# STM32WL_RF.net
KiCad netlist of a schematic drawn in Altium Designer
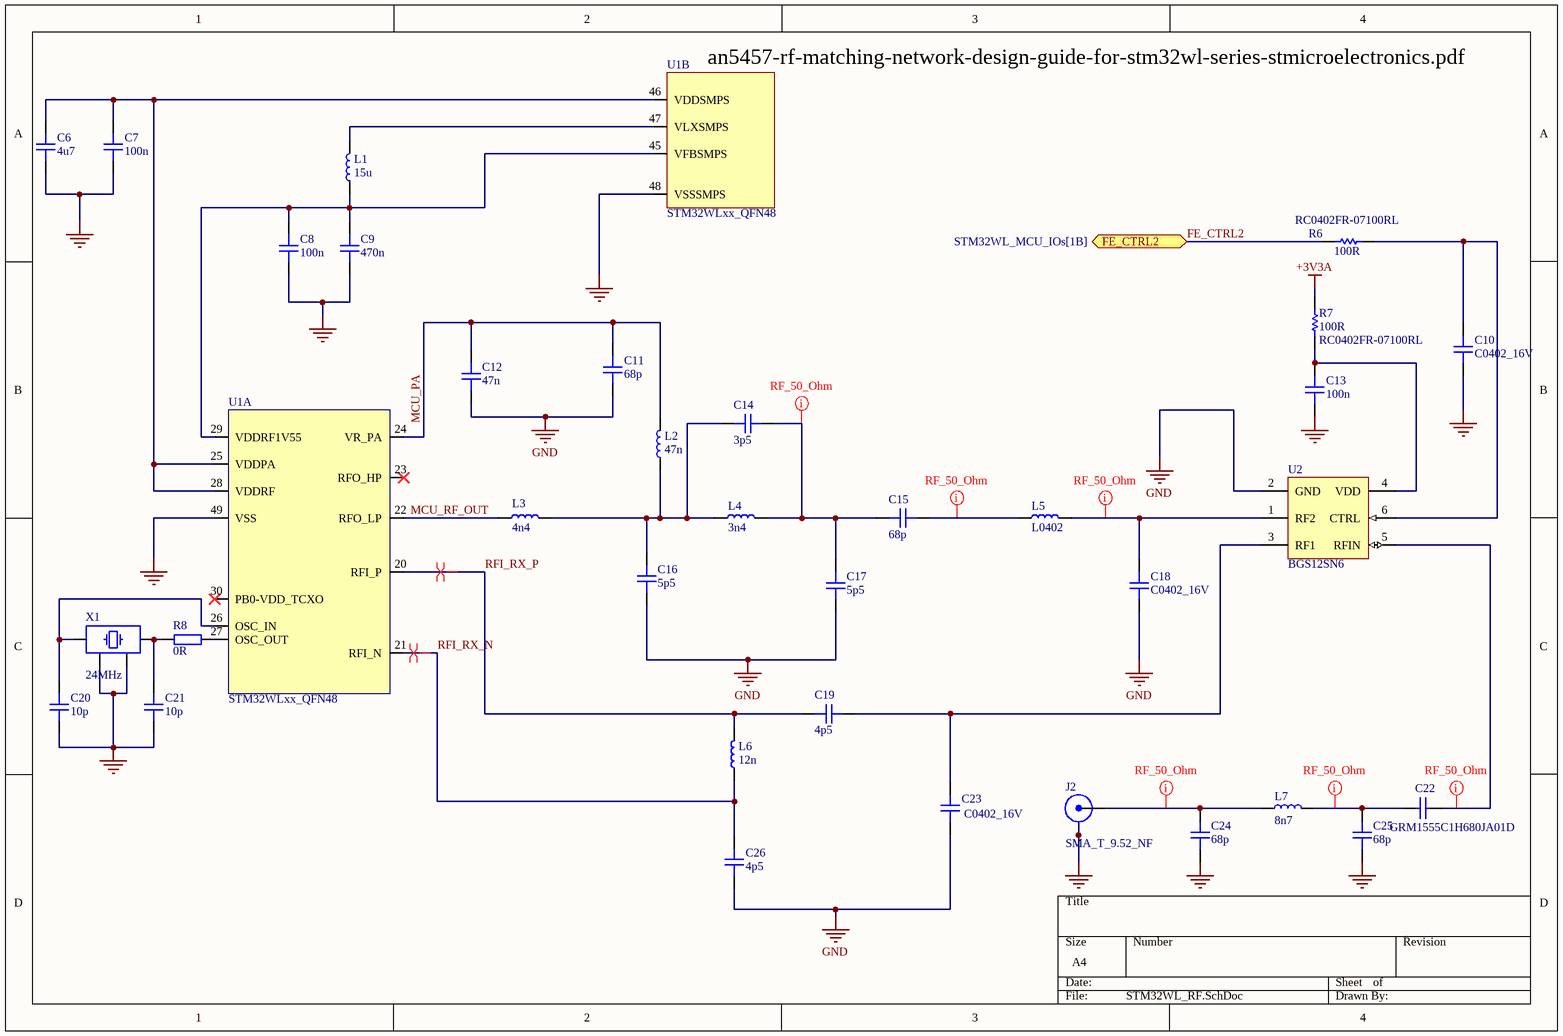
[diagram p0: STM32WL_RF.SchDoc]

(export (version "E")
  (design (tool "Eeschema 10.0.6"))
  (components
    (comp (ref "C6")
      (value "4u7")
      (footprint "CAP_0603")
      (description "Capacitor SMD 0201 16V")
      (libsource (lib "Schematic-Lib-PhilsLab") (part "CAP_0201_16V"))
    )
    (comp (ref "C7")
      (value "100n")
      (footprint "CAP_0603")
      (description "Capacitor SMD 0201 16V")
      (libsource (lib "Schematic-Lib-PhilsLab") (part "CAP_0201_16V"))
    )
    (comp (ref "C8")
      (value "100n")
      (footprint "CAP_0603")
      (description "Capacitor SMD 0201 16V")
      (libsource (lib "Schematic-Lib-PhilsLab") (part "CAP_0201_16V"))
    )
    (comp (ref "C9")
      (value "470n")
      (footprint "CAP_0603")
      (description "Capacitor SMD 0201 16V")
      (libsource (lib "Schematic-Lib-PhilsLab") (part "CAP_0201_16V"))
    )
    (comp (ref "C10")
      (value "C0402_16V")
      (footprint "CAP_0402")
      (description "Capacitor SMD 0402 16V")
      (libsource (lib "Schematic-Lib-PhilsLab") (part "CAP_0402_16V"))
    )
    (comp (ref "C11")
      (value "68p")
      (footprint "CAP_0402")
      (description "Capacitor SMD 0402 16V")
      (libsource (lib "Schematic-Lib-PhilsLab") (part "CAP_0402_16V"))
    )
    (comp (ref "C12")
      (value "47n")
      (footprint "CAP_0402")
      (description "Capacitor SMD 0402 16V")
      (libsource (lib "Schematic-Lib-PhilsLab") (part "CAP_0402_16V"))
    )
    (comp (ref "C13")
      (value "100n")
      (footprint "CAP_0402")
      (description "Capacitor SMD 0402 16V")
      (libsource (lib "Schematic-Lib-PhilsLab") (part "CAP_0402_16V"))
    )
    (comp (ref "C14")
      (value "3p5")
      (footprint "CAP_0402")
      (description "Capacitor SMD 0402 16V")
      (libsource (lib "Schematic-Lib-PhilsLab") (part "CAP_0402_16V"))
    )
    (comp (ref "C15")
      (value "68p")
      (footprint "CAP_0402")
      (description "Capacitor SMD 0402 16V")
      (libsource (lib "Schematic-Lib-PhilsLab") (part "CAP_0402_16V"))
    )
    (comp (ref "C16")
      (value "5p5")
      (footprint "CAP_0402")
      (description "Capacitor SMD 0402 16V")
      (libsource (lib "Schematic-Lib-PhilsLab") (part "CAP_0402_16V"))
    )
    (comp (ref "C17")
      (value "5p5")
      (footprint "CAP_0402")
      (description "Capacitor SMD 0402 16V")
      (libsource (lib "Schematic-Lib-PhilsLab") (part "CAP_0402_16V"))
    )
    (comp (ref "C18")
      (value "C0402_16V")
      (footprint "CAP_0402")
      (description "Capacitor SMD 0402 16V")
      (libsource (lib "Schematic-Lib-PhilsLab") (part "CAP_0402_16V"))
    )
    (comp (ref "C19")
      (value "4p5")
      (footprint "CAP_0402")
      (description "Capacitor SMD 0402 16V")
      (libsource (lib "Schematic-Lib-PhilsLab") (part "CAP_0402_16V"))
    )
    (comp (ref "C20")
      (value "10p")
      (footprint "CAP_0402")
      (description "Capacitor SMD 0402 16V")
      (libsource (lib "Schematic-Lib-PhilsLab") (part "CAP_0402_16V"))
    )
    (comp (ref "C21")
      (value "10p")
      (footprint "CAP_0402")
      (description "Capacitor SMD 0402 16V")
      (libsource (lib "Schematic-Lib-PhilsLab") (part "CAP_0402_16V"))
    )
    (comp (ref "C22")
      (value "GRM1555C1H680JA01D")
      (footprint "CAPC1005X55X25LL05T10")
      (fields (field (name "MANUFACTURER") "Murata"))
      (libsource (lib "Altium Content Vault") (part "CAP"))
    )
    (comp (ref "C23")
      (value "C0402_16V")
      (footprint "CAP_0402")
      (description "Capacitor SMD 0402 16V")
      (libsource (lib "Schematic-Lib-PhilsLab") (part "CAP_0402_16V"))
    )
    (comp (ref "C24")
      (value "68p")
      (footprint "CAP_0402")
      (description "Capacitor SMD 0402 16V")
      (libsource (lib "Schematic-Lib-PhilsLab") (part "CAP_0402_16V"))
    )
    (comp (ref "C25")
      (value "68p")
      (footprint "CAP_0402")
      (description "Capacitor SMD 0402 16V")
      (libsource (lib "Schematic-Lib-PhilsLab") (part "CAP_0402_16V"))
    )
    (comp (ref "C26")
      (value "4p5")
      (footprint "CAP_0402")
      (libsource (lib "Schematic-Lib-PhilsLab") (part "CAP_0402_16V"))
    )
    (comp (ref "J2")
      (value "SMA_T_9.52_NF")
      (footprint "CO_SAMTEC_SMA-J-P-ST-EMI")
      (description "SMA End Launch Jack 1.0 mm Board, 50 ohm")
      (fields
        (field (name "MANUFACTURER") "COAX CONNECTORS LTD")
        (field (name "MANUFACTURER_PART_NUMBER") "30-462-D3-1.1mm")
      )
      (libsource (lib "MB1789_HP") (part "SMA_T_9.52_NF"))
    )
    (comp (ref "L1")
      (value "15u")
      (footprint "IND_0402")
      (description "Inductor SMD 0402")
      (libsource (lib "Schematic-Lib-PhilsLab") (part "IND_0402"))
    )
    (comp (ref "L2")
      (value "47n")
      (footprint "IND_0402")
      (description "Inductor SMD 0402")
      (libsource (lib "Schematic-Lib-PhilsLab") (part "IND_0402"))
    )
    (comp (ref "L3")
      (value "4n4")
      (footprint "IND_0402")
      (description "Inductor SMD 0402 LQW15AN4N4G80D")
      (libsource (lib "Schematic-Lib-PhilsLab") (part "IND_0402"))
    )
    (comp (ref "L4")
      (value "3n4")
      (footprint "IND_0402")
      (description "Inductor SMD 0402")
      (libsource (lib "Schematic-Lib-PhilsLab") (part "IND_0402"))
    )
    (comp (ref "L5")
      (value "L0402")
      (footprint "IND_0402")
      (description "Inductor SMD 0402")
      (libsource (lib "Schematic-Lib-PhilsLab") (part "IND_0402"))
    )
    (comp (ref "L6")
      (value "12n")
      (footprint "IND_0402")
      (description "Inductor SMD 0402")
      (libsource (lib "Schematic-Lib-PhilsLab") (part "IND_0402"))
    )
    (comp (ref "L7")
      (value "8n7")
      (footprint "IND_0402")
      (description "Inductor SMD 0402")
      (libsource (lib "Schematic-Lib-PhilsLab") (part "IND_0402"))
    )
    (comp (ref "R6")
      (value "100R")
      (footprint "R0402")
      (description "Resistor,100R,0402,1%,1/16W")
      (fields
        (field (name "INTERNAL_PART_NUMBER") "MCD-00119")
        (field (name "MANUFACTURER_PART_NUMBER") "RC0402FR-07100RL")
        (field (name "MANUFACTURER") "YAGEO")
        (field (name "PROVIDED_BY") "SUBCO")
      )
      (libsource (lib "MCD_PARTS_database") (part "Resistor"))
    )
    (comp (ref "R7")
      (value "100R")
      (footprint "R0402")
      (description "Resistor,100R,0402,1%,1/16W")
      (fields
        (field (name "INTERNAL_PART_NUMBER") "MCD-00119")
        (field (name "MANUFACTURER_PART_NUMBER") "RC0402FR-07100RL")
        (field (name "MANUFACTURER") "YAGEO")
        (field (name "PROVIDED_BY") "SUBCO")
      )
      (libsource (lib "MCD_PARTS_database") (part "Resistor"))
    )
    (comp (ref "R8")
      (value "0R")
      (footprint "RES_0402")
      (description "Resistor SMD 0402")
      (libsource (lib "Schematic-Lib-PhilsLab") (part "RES_0402"))
    )
    (comp (ref "U1")
      (value "STM32WLxx_QFN48")
      (footprint "STM32WLxx_QFN48")
      (description "HQDC : Verified April, 25 2019")
      (fields
        (field (name "MANUFACTURER") "STMicroelectronics")
        (field (name "MANUFACTURER_PART_NUMBER") "STM32WLE5CC")
      )
      (libsource (lib "MB1789_HP") (part "STM32WLxx_QFN48"))
    )
    (comp (ref "U2")
      (value "BGS12SN6")
      (footprint "INF-TSNP-6-2_V")
      (description "Wideband RF SPDT Switch, 0.1 to 6 GHz, TSNP-6, Reel, Green")
      (fields (field (name "MANUFACTURER") "Infineon"))
      (libsource (lib "Altium Content Vault") (part "INF-BGS12PL_SL6-TSLP-6-4-6"))
    )
    (comp (ref "X1")
      (value "24MHz")
      (footprint "XTAL_3225")
      (description "Crystal SMD 24MHz 10PPM 7pF 3225")
      (fields (field (name "MANUFACTURER") "Epson"))
      (libsource (lib "Schematic-Lib-PhilsLab") (part "TSX-3225_24.0000MF15X-AC"))
    )
  )
  (nets
    (net (code "1") (name "+3V3A") (class "Default")
      (node (ref "R7") (pin "2") (pinfunction "2_2") (pintype "passive"))
    )
    (net (code "2") (name "/FE_CTRL2") (class "Default")
      (node (ref "R6") (pin "1") (pinfunction "1_1") (pintype "passive"))
    )
    (net (code "3") (name "/MCU_PA") (class "Default")
      (node (ref "C11") (pin "2") (pinfunction "2_2") (pintype "passive"))
      (node (ref "C12") (pin "2") (pinfunction "2_2") (pintype "passive"))
      (node (ref "L2") (pin "2") (pinfunction "2_2") (pintype "passive"))
      (node (ref "U1") (pin "24") (pinfunction "VR_PA_24") (pintype "passive"))
    )
    (net (code "4") (name "/MCU_RF_OUT") (class "Default")
      (node (ref "L3") (pin "1") (pinfunction "1_1") (pintype "passive"))
      (node (ref "U1") (pin "22") (pinfunction "RFO_LP_22") (pintype "passive"))
    )
    (net (code "5") (name "/RFI_RX_N") (class "Default")
      (node (ref "C26") (pin "2") (pinfunction "2_2") (pintype "passive"))
      (node (ref "L6") (pin "1") (pinfunction "1_1") (pintype "passive"))
      (node (ref "U1") (pin "21") (pinfunction "RFI_N_21") (pintype "passive"))
    )
    (net (code "6") (name "/RFI_RX_P") (class "Default")
      (node (ref "C19") (pin "1") (pinfunction "1_1") (pintype "passive"))
      (node (ref "L6") (pin "2") (pinfunction "2_2") (pintype "passive"))
      (node (ref "U1") (pin "20") (pinfunction "RFI_P_20") (pintype "passive"))
    )
    (net (code "7") (name "GND") (class "Default")
      (node (ref "C10") (pin "1") (pinfunction "1_1") (pintype "passive"))
      (node (ref "C11") (pin "1") (pinfunction "1_1") (pintype "passive"))
      (node (ref "C12") (pin "1") (pinfunction "1_1") (pintype "passive"))
      (node (ref "C13") (pin "1") (pinfunction "1_1") (pintype "passive"))
      (node (ref "C16") (pin "1") (pinfunction "1_1") (pintype "passive"))
      (node (ref "C17") (pin "1") (pinfunction "1_1") (pintype "passive"))
      (node (ref "C18") (pin "1") (pinfunction "1_1") (pintype "passive"))
      (node (ref "C20") (pin "1") (pinfunction "1_1") (pintype "passive"))
      (node (ref "C21") (pin "1") (pinfunction "1_1") (pintype "passive"))
      (node (ref "C23") (pin "1") (pinfunction "1_1") (pintype "passive"))
      (node (ref "C24") (pin "1") (pinfunction "1_1") (pintype "passive"))
      (node (ref "C25") (pin "1") (pinfunction "1_1") (pintype "passive"))
      (node (ref "C26") (pin "1") (pinfunction "1_1") (pintype "passive"))
      (node (ref "C6") (pin "1") (pinfunction "1_1") (pintype "passive"))
      (node (ref "C7") (pin "1") (pinfunction "1_1") (pintype "passive"))
      (node (ref "C8") (pin "1") (pinfunction "1_1") (pintype "passive"))
      (node (ref "C9") (pin "1") (pinfunction "1_1") (pintype "passive"))
      (node (ref "J2") (pin "2") (pinfunction "Y_2") (pintype "passive"))
      (node (ref "U1") (pin "48") (pinfunction "VSSSMPS_48") (pintype "passive"))
      (node (ref "U1") (pin "49") (pinfunction "VSS_49") (pintype "passive"))
      (node (ref "U2") (pin "2") (pinfunction "GND_2") (pintype "power_in"))
      (node (ref "X1") (pin "2") (pinfunction "2_2") (pintype "passive"))
      (node (ref "X1") (pin "4") (pinfunction "4_4") (pintype "passive"))
    )
    (net (code "8") (name "Net-(C14-Pad1)") (class "Default")
      (node (ref "C14") (pin "1") (pinfunction "1_1") (pintype "passive"))
      (node (ref "C16") (pin "2") (pinfunction "2_2") (pintype "passive"))
      (node (ref "L2") (pin "1") (pinfunction "1_1") (pintype "passive"))
      (node (ref "L3") (pin "2") (pinfunction "2_2") (pintype "passive"))
      (node (ref "L4") (pin "1") (pinfunction "1_1") (pintype "passive"))
    )
    (net (code "9") (name "Net-(C14-Pad2)") (class "Default")
      (node (ref "C14") (pin "2") (pinfunction "2_2") (pintype "passive"))
      (node (ref "C15") (pin "1") (pinfunction "1_1") (pintype "passive"))
      (node (ref "C17") (pin "2") (pinfunction "2_2") (pintype "passive"))
      (node (ref "L4") (pin "2") (pinfunction "2_2") (pintype "passive"))
    )
    (net (code "10") (name "Net-(C15-Pad2)") (class "Default")
      (node (ref "C15") (pin "2") (pinfunction "2_2") (pintype "passive"))
      (node (ref "L5") (pin "1") (pinfunction "1_1") (pintype "passive"))
    )
    (net (code "11") (name "Net-(C21-Pad2)") (class "Default")
      (node (ref "C21") (pin "2") (pinfunction "2_2") (pintype "passive"))
      (node (ref "R8") (pin "1") (pinfunction "1_1") (pintype "passive"))
      (node (ref "X1") (pin "3") (pinfunction "3_3") (pintype "passive"))
    )
    (net (code "12") (name "Net-(C22-Pad1)") (class "Default")
      (node (ref "C22") (pin "1") (pinfunction "1_1") (pintype "passive"))
      (node (ref "C25") (pin "2") (pinfunction "2_2") (pintype "passive"))
      (node (ref "L7") (pin "2") (pinfunction "2_2") (pintype "passive"))
    )
    (net (code "13") (name "Net-(J2-X)") (class "Default")
      (node (ref "C24") (pin "2") (pinfunction "2_2") (pintype "passive"))
      (node (ref "J2") (pin "1") (pinfunction "X_1") (pintype "passive"))
      (node (ref "L7") (pin "1") (pinfunction "1_1") (pintype "passive"))
    )
    (net (code "14") (name "Net-(U1A-OSC_IN)") (class "Default")
      (node (ref "C20") (pin "2") (pinfunction "2_2") (pintype "passive"))
      (node (ref "U1") (pin "26") (pinfunction "OSC_IN_26") (pintype "passive"))
      (node (ref "X1") (pin "1") (pinfunction "1_1") (pintype "passive"))
    )
    (net (code "15") (name "Net-(U1A-OSC_OUT)") (class "Default")
      (node (ref "R8") (pin "2") (pinfunction "2_2") (pintype "passive"))
      (node (ref "U1") (pin "27") (pinfunction "OSC_OUT_27") (pintype "passive"))
    )
    (net (code "16") (name "Net-(U1A-VDDPA)") (class "Default")
      (node (ref "C6") (pin "2") (pinfunction "2_2") (pintype "passive"))
      (node (ref "C7") (pin "2") (pinfunction "2_2") (pintype "passive"))
      (node (ref "U1") (pin "25") (pinfunction "VDDPA_25") (pintype "passive"))
      (node (ref "U1") (pin "28") (pinfunction "VDDRF_28") (pintype "passive"))
      (node (ref "U1") (pin "46") (pinfunction "VDDSMPS_46") (pintype "passive"))
    )
    (net (code "17") (name "Net-(U1A-VDDRF1V55)") (class "Default")
      (node (ref "C8") (pin "2") (pinfunction "2_2") (pintype "passive"))
      (node (ref "C9") (pin "2") (pinfunction "2_2") (pintype "passive"))
      (node (ref "L1") (pin "1") (pinfunction "1_1") (pintype "passive"))
      (node (ref "U1") (pin "29") (pinfunction "VDDRF1V55_29") (pintype "passive"))
      (node (ref "U1") (pin "45") (pinfunction "VFBSMPS_45") (pintype "passive"))
    )
    (net (code "18") (name "Net-(U1B-VLXSMPS)") (class "Default")
      (node (ref "L1") (pin "2") (pinfunction "2_2") (pintype "passive"))
      (node (ref "U1") (pin "47") (pinfunction "VLXSMPS_47") (pintype "passive"))
    )
    (net (code "19") (name "Net-(U2-CTRL)") (class "Default")
      (node (ref "C10") (pin "2") (pinfunction "2_2") (pintype "passive"))
      (node (ref "R6") (pin "2") (pinfunction "2_2") (pintype "passive"))
      (node (ref "U2") (pin "6") (pinfunction "CTRL_6") (pintype "input"))
    )
    (net (code "20") (name "Net-(U2-RF1)") (class "Default")
      (node (ref "C19") (pin "2") (pinfunction "2_2") (pintype "passive"))
      (node (ref "C23") (pin "2") (pinfunction "2_2") (pintype "passive"))
      (node (ref "U2") (pin "3") (pinfunction "RF1_3") (pintype "passive"))
    )
    (net (code "21") (name "Net-(U2-RF2)") (class "Default")
      (node (ref "C18") (pin "2") (pinfunction "2_2") (pintype "passive"))
      (node (ref "L5") (pin "2") (pinfunction "2_2") (pintype "passive"))
      (node (ref "U2") (pin "1") (pinfunction "RF2_1") (pintype "passive"))
    )
    (net (code "22") (name "Net-(U2-RFIN)") (class "Default")
      (node (ref "C22") (pin "2") (pinfunction "2_2") (pintype "passive"))
      (node (ref "U2") (pin "5") (pinfunction "RFIN_5") (pintype "bidirectional"))
    )
    (net (code "23") (name "Net-(U2-VDD)") (class "Default")
      (node (ref "C13") (pin "2") (pinfunction "2_2") (pintype "passive"))
      (node (ref "R7") (pin "1") (pinfunction "1_1") (pintype "passive"))
      (node (ref "U2") (pin "4") (pinfunction "VDD_4") (pintype "power_in"))
    )
    (net (code "24") (name "unconnected-(U1A-PB0-VDD_TCXO-Pad30)") (class "Default")
      (node (ref "U1") (pin "30") (pinfunction "PB0-VDD_TCXO_30") (pintype "passive+no_connect"))
    )
    (net (code "25") (name "unconnected-(U1A-RFO_HP-Pad23)") (class "Default")
      (node (ref "U1") (pin "23") (pinfunction "RFO_HP_23") (pintype "passive+no_connect"))
    )
  )
)
